# mcp9808_breakout.net
KiCad netlist of a schematic drawn in EAGLE
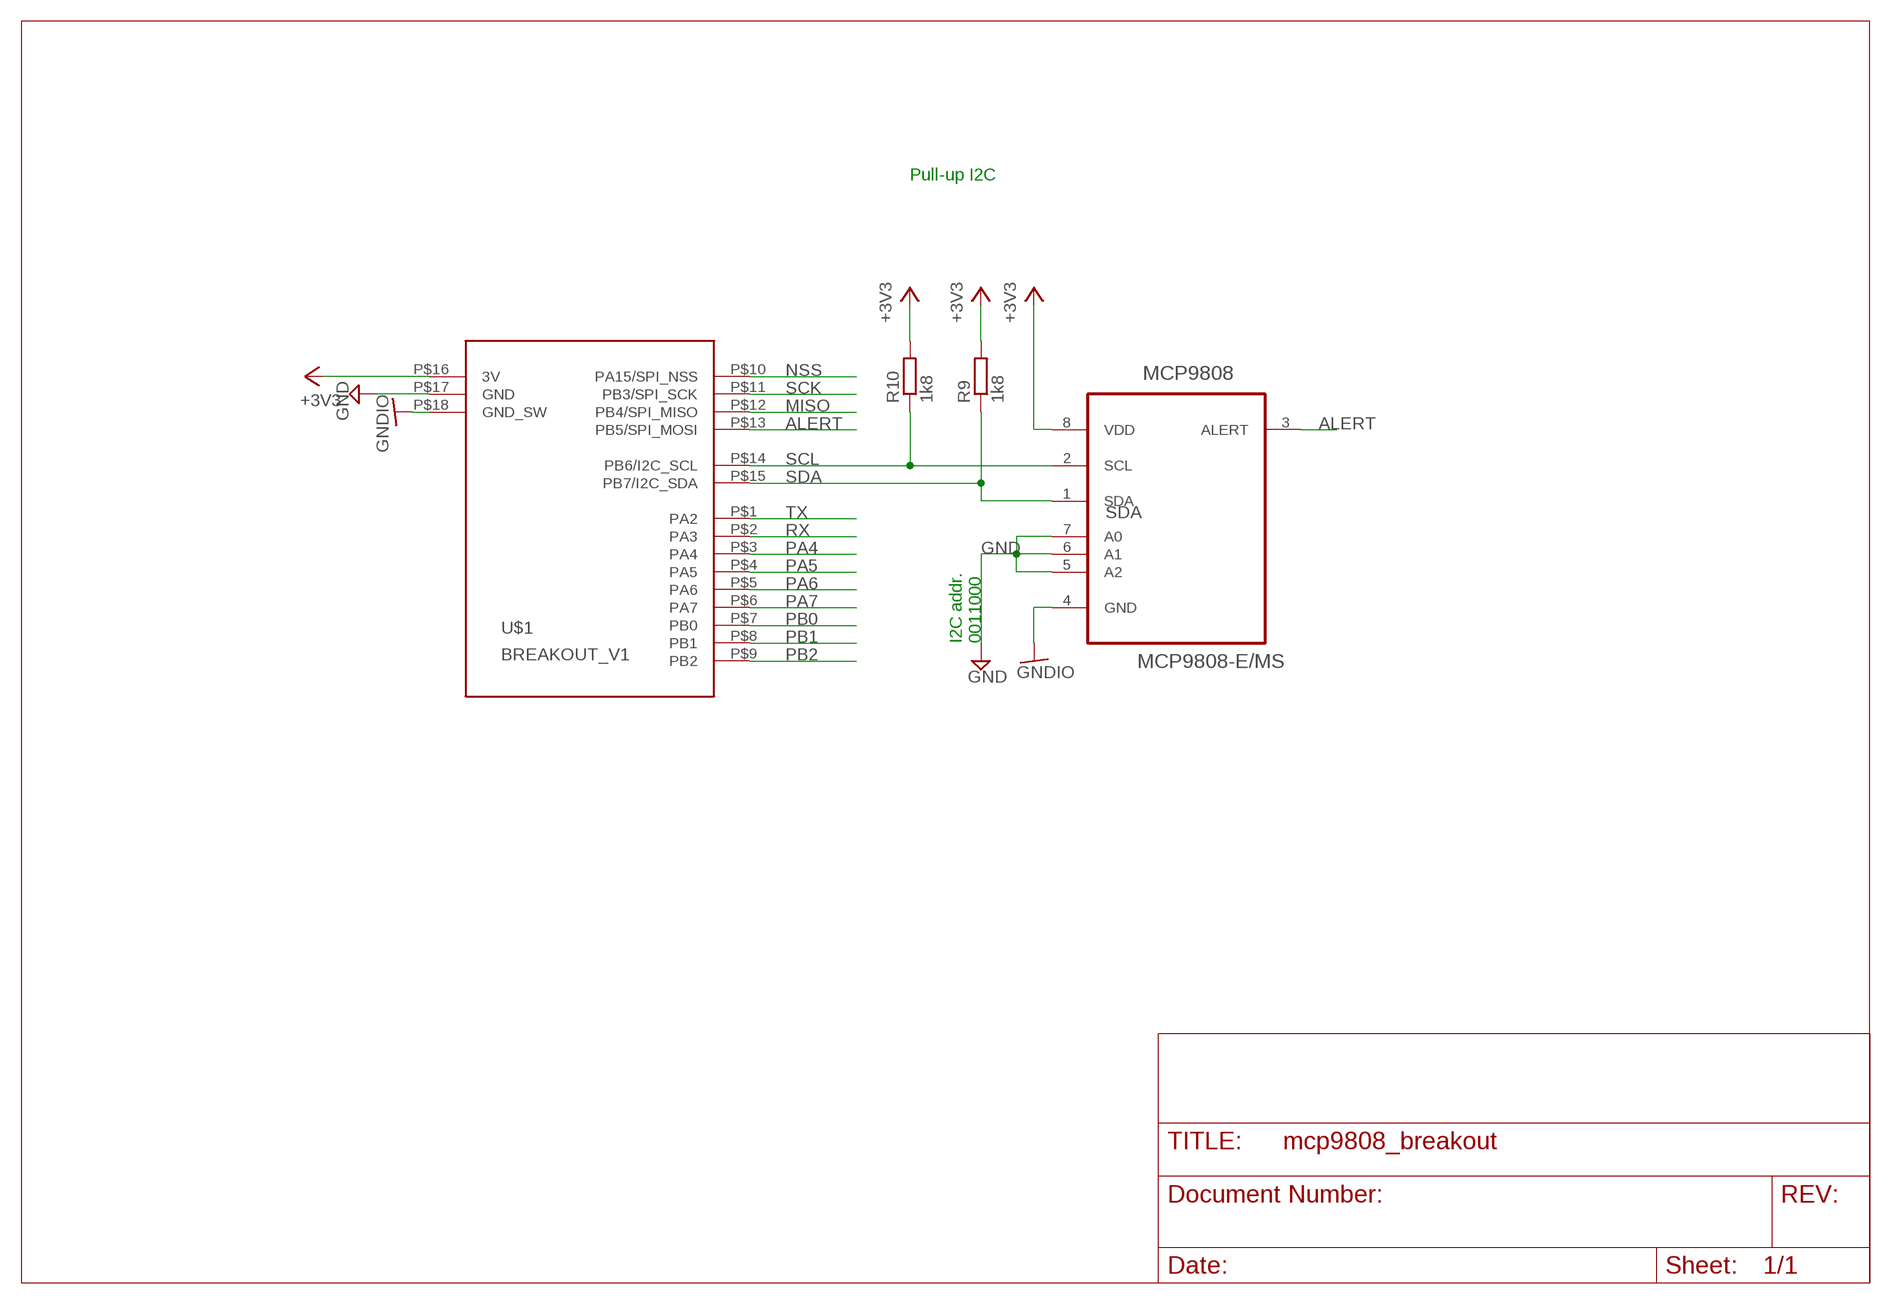
[diagram p0: schematic, sheet 1]

(export (version "E")
  (design (tool "Eeschema 10.0.6"))
  (components
    (comp (ref "MCP9808")
      (value "MCP9808-E/MS")
      (footprint "eagle-import:SOP65P490X110-8N")
      (libsource (lib "eagle-import") (part "MCP9808-E/MS"))
    )
    (comp (ref "R9")
      (value "1k8")
      (footprint "eagle-import:R0805")
      (libsource (lib "eagle-import") (part "R-EU_R0805"))
    )
    (comp (ref "R10")
      (value "1k8")
      (footprint "eagle-import:R0805")
      (libsource (lib "eagle-import") (part "R-EU_R0805"))
    )
    (comp (ref "U$1")
      (value "BREAKOUT_V1")
      (footprint "eagle-import:BREAKOUT_V1")
      (libsource (lib "eagle-import") (part "BREAKOUT_V1"))
    )
  )
  (nets
    (net (code "1") (name "+3V3") (class "Default")
      (node (ref "MCP9808") (pin "8") (pinfunction "VDD_8") (pintype "power_in"))
      (node (ref "R10") (pin "2") (pinfunction "2_2") (pintype "passive"))
      (node (ref "R9") (pin "2") (pinfunction "2_2") (pintype "passive"))
      (node (ref "U$1") (pin "P$16") (pinfunction "3V_P$16") (pintype "bidirectional"))
    )
    (net (code "2") (name "/ALERT") (class "Default")
      (node (ref "MCP9808") (pin "3") (pinfunction "ALERT_3") (pintype "output"))
      (node (ref "U$1") (pin "P$13") (pinfunction "PB5/SPI_MOSI_P$13") (pintype "bidirectional"))
    )
    (net (code "3") (name "/MISO") (class "Default")
      (node (ref "U$1") (pin "P$12") (pinfunction "PB4/SPI_MISO_P$12") (pintype "bidirectional"))
    )
    (net (code "4") (name "/NSS") (class "Default")
      (node (ref "U$1") (pin "P$10") (pinfunction "PA15/SPI_NSS_P$10") (pintype "bidirectional"))
    )
    (net (code "5") (name "/PA4") (class "Default")
      (node (ref "U$1") (pin "P$3") (pinfunction "PA4_P$3") (pintype "bidirectional"))
    )
    (net (code "6") (name "/PA5") (class "Default")
      (node (ref "U$1") (pin "P$4") (pinfunction "PA5_P$4") (pintype "bidirectional"))
    )
    (net (code "7") (name "/PA6") (class "Default")
      (node (ref "U$1") (pin "P$5") (pinfunction "PA6_P$5") (pintype "bidirectional"))
    )
    (net (code "8") (name "/PA7") (class "Default")
      (node (ref "U$1") (pin "P$6") (pinfunction "PA7_P$6") (pintype "bidirectional"))
    )
    (net (code "9") (name "/PB0") (class "Default")
      (node (ref "U$1") (pin "P$7") (pinfunction "PB0_P$7") (pintype "bidirectional"))
    )
    (net (code "10") (name "/PB1") (class "Default")
      (node (ref "U$1") (pin "P$8") (pinfunction "PB1_P$8") (pintype "bidirectional"))
    )
    (net (code "11") (name "/PB2") (class "Default")
      (node (ref "U$1") (pin "P$9") (pinfunction "PB2_P$9") (pintype "bidirectional"))
    )
    (net (code "12") (name "/RX") (class "Default")
      (node (ref "U$1") (pin "P$2") (pinfunction "PA3_P$2") (pintype "bidirectional"))
    )
    (net (code "13") (name "/SCK") (class "Default")
      (node (ref "U$1") (pin "P$11") (pinfunction "PB3/SPI_SCK_P$11") (pintype "bidirectional"))
    )
    (net (code "14") (name "/SCL") (class "Default")
      (node (ref "MCP9808") (pin "2") (pinfunction "SCL_2") (pintype "input"))
      (node (ref "R10") (pin "1") (pinfunction "1_1") (pintype "passive"))
      (node (ref "U$1") (pin "P$14") (pinfunction "PB6/I2C_SCL_P$14") (pintype "bidirectional"))
    )
    (net (code "15") (name "/SDA") (class "Default")
      (node (ref "MCP9808") (pin "1") (pinfunction "SDA_1") (pintype "bidirectional"))
      (node (ref "R9") (pin "1") (pinfunction "1_1") (pintype "passive"))
      (node (ref "U$1") (pin "P$15") (pinfunction "PB7/I2C_SDA_P$15") (pintype "bidirectional"))
    )
    (net (code "16") (name "/TX") (class "Default")
      (node (ref "U$1") (pin "P$1") (pinfunction "PA2_P$1") (pintype "bidirectional"))
    )
    (net (code "17") (name "GND") (class "Default")
      (node (ref "MCP9808") (pin "5") (pinfunction "A2_5") (pintype "input"))
      (node (ref "MCP9808") (pin "6") (pinfunction "A1_6") (pintype "input"))
      (node (ref "MCP9808") (pin "7") (pinfunction "A0_7") (pintype "input"))
      (node (ref "U$1") (pin "P$17") (pinfunction "GND_P$17") (pintype "bidirectional"))
    )
    (net (code "18") (name "GNDIO") (class "Default")
      (node (ref "MCP9808") (pin "4") (pinfunction "GND_4") (pintype "passive"))
      (node (ref "U$1") (pin "P$18") (pinfunction "GND_SW_P$18") (pintype "bidirectional"))
    )
  )
)
